# howland_vccs_differential.net
KiCad netlist of a schematic drawn in EAGLE
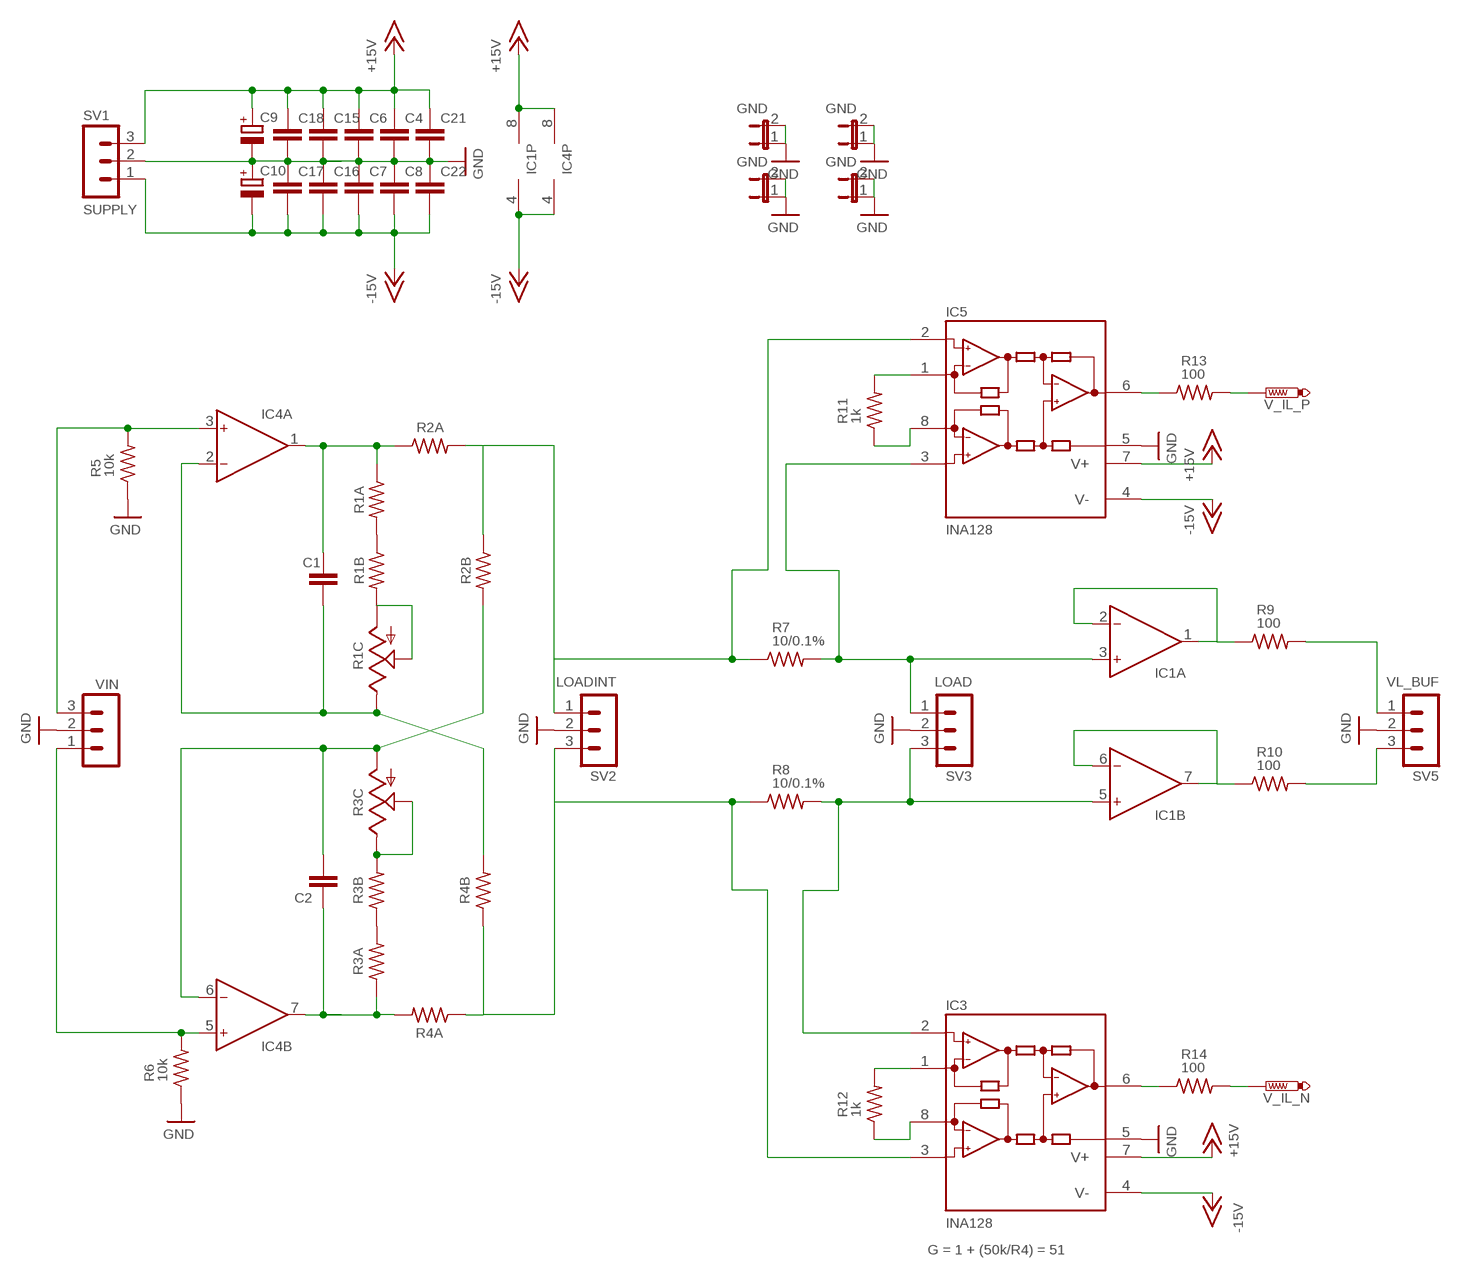
[diagram p0: schematic, sheet 1]

(export (version "E")
  (design (tool "Eeschema 10.0.6"))
  (components
    (comp (ref "C1")
      (value "C-EUC1206")
      (footprint "eagle-import:C1206")
      (libsource (lib "eagle-import") (part "C-EUC1206"))
    )
    (comp (ref "C2")
      (value "C-EUC1206")
      (footprint "eagle-import:C1206")
      (libsource (lib "eagle-import") (part "C-EUC1206"))
    )
    (comp (ref "C4")
      (value "C-EUC1206")
      (footprint "eagle-import:C1206")
      (libsource (lib "eagle-import") (part "C-EUC1206"))
    )
    (comp (ref "C6")
      (value "C-EUC1206")
      (footprint "eagle-import:C1206")
      (libsource (lib "eagle-import") (part "C-EUC1206"))
    )
    (comp (ref "C7")
      (value "C-EUC1206")
      (footprint "eagle-import:C1206")
      (libsource (lib "eagle-import") (part "C-EUC1206"))
    )
    (comp (ref "C8")
      (value "C-EUC1206")
      (footprint "eagle-import:C1206")
      (libsource (lib "eagle-import") (part "C-EUC1206"))
    )
    (comp (ref "C9")
      (value "CPOL-EUC/6032-28R")
      (footprint "eagle-import:C_6032-28R")
      (libsource (lib "eagle-import") (part "CPOL-EUC/6032-28R"))
    )
    (comp (ref "C10")
      (value "CPOL-EUC/6032-28R")
      (footprint "eagle-import:C_6032-28R")
      (libsource (lib "eagle-import") (part "CPOL-EUC/6032-28R"))
    )
    (comp (ref "C15")
      (value "C-EUC1206")
      (footprint "eagle-import:C1206")
      (libsource (lib "eagle-import") (part "C-EUC1206"))
    )
    (comp (ref "C16")
      (value "C-EUC1206")
      (footprint "eagle-import:C1206")
      (libsource (lib "eagle-import") (part "C-EUC1206"))
    )
    (comp (ref "C17")
      (value "C-EUC1206")
      (footprint "eagle-import:C1206")
      (libsource (lib "eagle-import") (part "C-EUC1206"))
    )
    (comp (ref "C18")
      (value "C-EUC1206")
      (footprint "eagle-import:C1206")
      (libsource (lib "eagle-import") (part "C-EUC1206"))
    )
    (comp (ref "C21")
      (value "C-EUC1206")
      (footprint "eagle-import:C1206")
      (libsource (lib "eagle-import") (part "C-EUC1206"))
    )
    (comp (ref "C22")
      (value "C-EUC1206")
      (footprint "eagle-import:C1206")
      (libsource (lib "eagle-import") (part "C-EUC1206"))
    )
    (comp (ref "IC1")
      (value "OPA2192")
      (footprint "eagle-import:SO8")
      (fields (field (name "MF") "ALTERA CORPORATION") (field (name "MPN") "AD826AR"))
      (libsource (lib "eagle-import") (part "AD826R"))
    )
    (comp (ref "IC3")
      (value "INA128")
      (footprint "eagle-import:SO08")
      (fields (field (name "MF") "TEXAS INSTRUMENTS") (field (name "MPN") "INA128U"))
      (libsource (lib "eagle-import") (part "INA128U"))
    )
    (comp (ref "IC4")
      (value "OPA2192")
      (footprint "eagle-import:SO8")
      (fields (field (name "MF") "ALTERA CORPORATION") (field (name "MPN") "AD826AR"))
      (libsource (lib "eagle-import") (part "AD826R"))
    )
    (comp (ref "IC5")
      (value "INA128")
      (footprint "eagle-import:SO08")
      (fields (field (name "MF") "TEXAS INSTRUMENTS") (field (name "MPN") "INA128U"))
      (libsource (lib "eagle-import") (part "INA128U"))
    )
    (comp (ref "JP8")
      (value "GND")
      (footprint "eagle-import:JP1")
      (libsource (lib "eagle-import") (part "JP1E"))
    )
    (comp (ref "JP10")
      (value "GND")
      (footprint "eagle-import:JP1")
      (libsource (lib "eagle-import") (part "JP1E"))
    )
    (comp (ref "JP11")
      (value "GND")
      (footprint "eagle-import:JP1")
      (libsource (lib "eagle-import") (part "JP1E"))
    )
    (comp (ref "JP12")
      (value "GND")
      (footprint "eagle-import:JP1")
      (libsource (lib "eagle-import") (part "JP1E"))
    )
    (comp (ref "R1A")
      (value "R-US_R1206")
      (footprint "eagle-import:R1206")
      (libsource (lib "eagle-import") (part "R-US_R1206"))
    )
    (comp (ref "R1B")
      (value "R-US_R1206")
      (footprint "eagle-import:R1206")
      (libsource (lib "eagle-import") (part "R-US_R1206"))
    )
    (comp (ref "R1C")
      (value "TRIM_US-3223J")
      (footprint "eagle-import:3223J")
      (libsource (lib "eagle-import") (part "TRIM_US-3223J"))
    )
    (comp (ref "R2A")
      (value "R-US_R1206")
      (footprint "eagle-import:R1206")
      (libsource (lib "eagle-import") (part "R-US_R1206"))
    )
    (comp (ref "R2B")
      (value "R-US_R1206")
      (footprint "eagle-import:R1206")
      (libsource (lib "eagle-import") (part "R-US_R1206"))
    )
    (comp (ref "R3A")
      (value "R-US_R1206")
      (footprint "eagle-import:R1206")
      (libsource (lib "eagle-import") (part "R-US_R1206"))
    )
    (comp (ref "R3B")
      (value "R-US_R1206")
      (footprint "eagle-import:R1206")
      (libsource (lib "eagle-import") (part "R-US_R1206"))
    )
    (comp (ref "R3C")
      (value "TRIM_US-3223J")
      (footprint "eagle-import:3223J")
      (libsource (lib "eagle-import") (part "TRIM_US-3223J"))
    )
    (comp (ref "R4A")
      (value "R-US_R1206")
      (footprint "eagle-import:R1206")
      (libsource (lib "eagle-import") (part "R-US_R1206"))
    )
    (comp (ref "R4B")
      (value "R-US_R1206")
      (footprint "eagle-import:R1206")
      (libsource (lib "eagle-import") (part "R-US_R1206"))
    )
    (comp (ref "R5")
      (value "10k")
      (footprint "eagle-import:R1206")
      (libsource (lib "eagle-import") (part "R-US_R1206"))
    )
    (comp (ref "R6")
      (value "10k")
      (footprint "eagle-import:R1206")
      (libsource (lib "eagle-import") (part "R-US_R1206"))
    )
    (comp (ref "R7")
      (value "10/0.1%")
      (footprint "eagle-import:R1206")
      (libsource (lib "eagle-import") (part "R-US_R1206"))
    )
    (comp (ref "R8")
      (value "10/0.1%")
      (footprint "eagle-import:R1206")
      (libsource (lib "eagle-import") (part "R-US_R1206"))
    )
    (comp (ref "R9")
      (value "100")
      (footprint "eagle-import:R1206")
      (libsource (lib "eagle-import") (part "R-US_R1206"))
    )
    (comp (ref "R10")
      (value "100")
      (footprint "eagle-import:R1206")
      (libsource (lib "eagle-import") (part "R-US_R1206"))
    )
    (comp (ref "R11")
      (value "1k")
      (footprint "eagle-import:R1206")
      (libsource (lib "eagle-import") (part "R-US_R1206"))
    )
    (comp (ref "R12")
      (value "1k")
      (footprint "eagle-import:R1206")
      (libsource (lib "eagle-import") (part "R-US_R1206"))
    )
    (comp (ref "R13")
      (value "100")
      (footprint "eagle-import:R1206")
      (libsource (lib "eagle-import") (part "R-US_R1206"))
    )
    (comp (ref "R14")
      (value "100")
      (footprint "eagle-import:R1206")
      (libsource (lib "eagle-import") (part "R-US_R1206"))
    )
    (comp (ref "SV1")
      (value "SUPPLY")
      (footprint "eagle-import:MA03-1")
      (libsource (lib "eagle-import") (part "MA03-1"))
    )
    (comp (ref "SV2")
      (value "LOADINT")
      (footprint "eagle-import:MA03-1")
      (libsource (lib "eagle-import") (part "sil_header_3_MA03-1"))
    )
    (comp (ref "SV3")
      (value "LOAD")
      (footprint "eagle-import:MA03-1")
      (libsource (lib "eagle-import") (part "sil_header_3_MA03-1"))
    )
    (comp (ref "SV5")
      (value "VL_BUF")
      (footprint "eagle-import:MA03-1")
      (libsource (lib "eagle-import") (part "sil_header_3_MA03-1"))
    )
    (comp (ref "VIN")
      (value "MA03-1")
      (footprint "eagle-import:MA03-1")
      (libsource (lib "eagle-import") (part "sil_header_3_MA03-1"))
    )
    (comp (ref "V_IL_N")
      (value "PTR1PAD1-13")
      (footprint "eagle-import:P1-13")
      (libsource (lib "eagle-import") (part "PTR1PAD1-13"))
    )
    (comp (ref "V_IL_P")
      (value "PTR1PAD1-13")
      (footprint "eagle-import:P1-13")
      (libsource (lib "eagle-import") (part "PTR1PAD1-13"))
    )
  )
  (nets
    (net (code "1") (name "+15V") (class "Default")
      (node (ref "C15") (pin "1") (pinfunction "1_1") (pintype "passive"))
      (node (ref "C18") (pin "1") (pinfunction "1_1") (pintype "passive"))
      (node (ref "C21") (pin "1") (pinfunction "1_1") (pintype "passive"))
      (node (ref "C4") (pin "1") (pinfunction "1_1") (pintype "passive"))
      (node (ref "C6") (pin "1") (pinfunction "1_1") (pintype "passive"))
      (node (ref "C9") (pin "+") (pinfunction "+_+") (pintype "passive"))
      (node (ref "IC1") (pin "8") (pinfunction "V+_8") (pintype "power_in"))
      (node (ref "IC3") (pin "7") (pinfunction "V+_7") (pintype "power_in"))
      (node (ref "IC4") (pin "8") (pinfunction "V+_8") (pintype "power_in"))
      (node (ref "IC5") (pin "7") (pinfunction "V+_7") (pintype "power_in"))
      (node (ref "SV1") (pin "3") (pinfunction "3_3") (pintype "passive"))
    )
    (net (code "2") (name "-15V") (class "Default")
      (node (ref "C10") (pin "-") (pinfunction "-_-") (pintype "passive"))
      (node (ref "C16") (pin "2") (pinfunction "2_2") (pintype "passive"))
      (node (ref "C17") (pin "2") (pinfunction "2_2") (pintype "passive"))
      (node (ref "C22") (pin "2") (pinfunction "2_2") (pintype "passive"))
      (node (ref "C7") (pin "2") (pinfunction "2_2") (pintype "passive"))
      (node (ref "C8") (pin "2") (pinfunction "2_2") (pintype "passive"))
      (node (ref "IC1") (pin "4") (pinfunction "V-_4") (pintype "power_in"))
      (node (ref "IC3") (pin "4") (pinfunction "V-_4") (pintype "power_in"))
      (node (ref "IC4") (pin "4") (pinfunction "V-_4") (pintype "power_in"))
      (node (ref "IC5") (pin "4") (pinfunction "V-_4") (pintype "power_in"))
      (node (ref "SV1") (pin "1") (pinfunction "1_1") (pintype "passive"))
    )
    (net (code "3") (name "GND") (class "Default")
      (node (ref "C10") (pin "+") (pinfunction "+_+") (pintype "passive"))
      (node (ref "C15") (pin "2") (pinfunction "2_2") (pintype "passive"))
      (node (ref "C16") (pin "1") (pinfunction "1_1") (pintype "passive"))
      (node (ref "C17") (pin "1") (pinfunction "1_1") (pintype "passive"))
      (node (ref "C18") (pin "2") (pinfunction "2_2") (pintype "passive"))
      (node (ref "C21") (pin "2") (pinfunction "2_2") (pintype "passive"))
      (node (ref "C22") (pin "1") (pinfunction "1_1") (pintype "passive"))
      (node (ref "C4") (pin "2") (pinfunction "2_2") (pintype "passive"))
      (node (ref "C6") (pin "2") (pinfunction "2_2") (pintype "passive"))
      (node (ref "C7") (pin "1") (pinfunction "1_1") (pintype "passive"))
      (node (ref "C8") (pin "1") (pinfunction "1_1") (pintype "passive"))
      (node (ref "C9") (pin "-") (pinfunction "-_-") (pintype "passive"))
      (node (ref "IC3") (pin "5") (pinfunction "REF_5") (pintype "passive"))
      (node (ref "IC5") (pin "5") (pinfunction "REF_5") (pintype "passive"))
      (node (ref "JP10") (pin "1") (pinfunction "1_1") (pintype "passive"))
      (node (ref "JP10") (pin "2") (pinfunction "2_2") (pintype "passive"))
      (node (ref "JP11") (pin "1") (pinfunction "1_1") (pintype "passive"))
      (node (ref "JP11") (pin "2") (pinfunction "2_2") (pintype "passive"))
      (node (ref "JP12") (pin "1") (pinfunction "1_1") (pintype "passive"))
      (node (ref "JP12") (pin "2") (pinfunction "2_2") (pintype "passive"))
      (node (ref "JP8") (pin "1") (pinfunction "1_1") (pintype "passive"))
      (node (ref "JP8") (pin "2") (pinfunction "2_2") (pintype "passive"))
      (node (ref "R5") (pin "1") (pinfunction "1_1") (pintype "passive"))
      (node (ref "R6") (pin "1") (pinfunction "1_1") (pintype "passive"))
      (node (ref "SV1") (pin "2") (pinfunction "2_2") (pintype "passive"))
      (node (ref "SV2") (pin "2") (pinfunction "2_2") (pintype "passive"))
      (node (ref "SV3") (pin "2") (pinfunction "2_2") (pintype "passive"))
      (node (ref "SV5") (pin "2") (pinfunction "2_2") (pintype "passive"))
      (node (ref "VIN") (pin "2") (pinfunction "2_2") (pintype "passive"))
    )
    (net (code "4") (name "Net-(IC1A-IN+)") (class "Default")
      (node (ref "IC1") (pin "3") (pinfunction "IN+_3") (pintype "input"))
      (node (ref "IC5") (pin "3") (pinfunction "+IN_3") (pintype "input"))
      (node (ref "R7") (pin "2") (pinfunction "2_2") (pintype "passive"))
      (node (ref "SV3") (pin "1") (pinfunction "1_1") (pintype "passive"))
    )
    (net (code "5") (name "Net-(IC1A-IN-)") (class "Default")
      (node (ref "IC1") (pin "1") (pinfunction "OUT_1") (pintype "output"))
      (node (ref "IC1") (pin "2") (pinfunction "IN-_2") (pintype "input"))
      (node (ref "R9") (pin "1") (pinfunction "1_1") (pintype "passive"))
    )
    (net (code "6") (name "Net-(IC1B-IN+)") (class "Default")
      (node (ref "IC1") (pin "5") (pinfunction "IN+_5") (pintype "input"))
      (node (ref "IC3") (pin "2") (pinfunction "-IN_2") (pintype "input"))
      (node (ref "R8") (pin "2") (pinfunction "2_2") (pintype "passive"))
      (node (ref "SV3") (pin "3") (pinfunction "3_3") (pintype "passive"))
    )
    (net (code "7") (name "Net-(IC1B-IN-)") (class "Default")
      (node (ref "IC1") (pin "6") (pinfunction "IN-_6") (pintype "input"))
      (node (ref "IC1") (pin "7") (pinfunction "OUT_7") (pintype "output"))
      (node (ref "R10") (pin "1") (pinfunction "1_1") (pintype "passive"))
    )
    (net (code "8") (name "Net-(IC3-+IN)") (class "Default")
      (node (ref "IC3") (pin "3") (pinfunction "+IN_3") (pintype "input"))
      (node (ref "R4A") (pin "1") (pinfunction "1_1") (pintype "passive"))
      (node (ref "R4B") (pin "1") (pinfunction "1_1") (pintype "passive"))
      (node (ref "R8") (pin "1") (pinfunction "1_1") (pintype "passive"))
      (node (ref "SV2") (pin "3") (pinfunction "3_3") (pintype "passive"))
    )
    (net (code "9") (name "Net-(IC3-OUT)") (class "Default")
      (node (ref "IC3") (pin "6") (pinfunction "OUT_6") (pintype "output"))
      (node (ref "R14") (pin "1") (pinfunction "1_1") (pintype "passive"))
    )
    (net (code "10") (name "Net-(IC3-RG-Pad1)") (class "Default")
      (node (ref "IC3") (pin "1") (pinfunction "RG_1") (pintype "passive"))
      (node (ref "R12") (pin "2") (pinfunction "2_2") (pintype "passive"))
    )
    (net (code "11") (name "Net-(IC3-RG-Pad8)") (class "Default")
      (node (ref "IC3") (pin "8") (pinfunction "RG_8") (pintype "passive"))
      (node (ref "R12") (pin "1") (pinfunction "1_1") (pintype "passive"))
    )
    (net (code "12") (name "Net-(IC4A-IN+)") (class "Default")
      (node (ref "IC4") (pin "3") (pinfunction "IN+_3") (pintype "input"))
      (node (ref "R5") (pin "2") (pinfunction "2_2") (pintype "passive"))
      (node (ref "VIN") (pin "3") (pinfunction "3_3") (pintype "passive"))
    )
    (net (code "13") (name "Net-(IC4A-IN-)") (class "Default")
      (node (ref "C1") (pin "2") (pinfunction "2_2") (pintype "passive"))
      (node (ref "IC4") (pin "2") (pinfunction "IN-_2") (pintype "input"))
      (node (ref "R1C") (pin "3") (pinfunction "E_3") (pintype "passive"))
      (node (ref "R4B") (pin "2") (pinfunction "2_2") (pintype "passive"))
    )
    (net (code "14") (name "Net-(IC4A-OUT)") (class "Default")
      (node (ref "C1") (pin "1") (pinfunction "1_1") (pintype "passive"))
      (node (ref "IC4") (pin "1") (pinfunction "OUT_1") (pintype "output"))
      (node (ref "R1A") (pin "1") (pinfunction "1_1") (pintype "passive"))
      (node (ref "R2A") (pin "1") (pinfunction "1_1") (pintype "passive"))
    )
    (net (code "15") (name "Net-(IC4B-IN+)") (class "Default")
      (node (ref "IC4") (pin "5") (pinfunction "IN+_5") (pintype "input"))
      (node (ref "R6") (pin "2") (pinfunction "2_2") (pintype "passive"))
      (node (ref "VIN") (pin "1") (pinfunction "1_1") (pintype "passive"))
    )
    (net (code "16") (name "Net-(IC4B-IN-)") (class "Default")
      (node (ref "C2") (pin "2") (pinfunction "2_2") (pintype "passive"))
      (node (ref "IC4") (pin "6") (pinfunction "IN-_6") (pintype "input"))
      (node (ref "R2B") (pin "2") (pinfunction "2_2") (pintype "passive"))
      (node (ref "R3C") (pin "1") (pinfunction "A_1") (pintype "passive"))
    )
    (net (code "17") (name "Net-(IC4B-OUT)") (class "Default")
      (node (ref "C2") (pin "1") (pinfunction "1_1") (pintype "passive"))
      (node (ref "IC4") (pin "7") (pinfunction "OUT_7") (pintype "output"))
      (node (ref "R3A") (pin "1") (pinfunction "1_1") (pintype "passive"))
      (node (ref "R4A") (pin "2") (pinfunction "2_2") (pintype "passive"))
    )
    (net (code "18") (name "Net-(IC5--IN)") (class "Default")
      (node (ref "IC5") (pin "2") (pinfunction "-IN_2") (pintype "input"))
      (node (ref "R2A") (pin "2") (pinfunction "2_2") (pintype "passive"))
      (node (ref "R2B") (pin "1") (pinfunction "1_1") (pintype "passive"))
      (node (ref "R7") (pin "1") (pinfunction "1_1") (pintype "passive"))
      (node (ref "SV2") (pin "1") (pinfunction "1_1") (pintype "passive"))
    )
    (net (code "19") (name "Net-(IC5-OUT)") (class "Default")
      (node (ref "IC5") (pin "6") (pinfunction "OUT_6") (pintype "output"))
      (node (ref "R13") (pin "1") (pinfunction "1_1") (pintype "passive"))
    )
    (net (code "20") (name "Net-(IC5-RG-Pad1)") (class "Default")
      (node (ref "IC5") (pin "1") (pinfunction "RG_1") (pintype "passive"))
      (node (ref "R11") (pin "2") (pinfunction "2_2") (pintype "passive"))
    )
    (net (code "21") (name "Net-(IC5-RG-Pad8)") (class "Default")
      (node (ref "IC5") (pin "8") (pinfunction "RG_8") (pintype "passive"))
      (node (ref "R11") (pin "1") (pinfunction "1_1") (pintype "passive"))
    )
    (net (code "22") (name "Net-(R1A-Pad2)") (class "Default")
      (node (ref "R1A") (pin "2") (pinfunction "2_2") (pintype "passive"))
      (node (ref "R1B") (pin "1") (pinfunction "1_1") (pintype "passive"))
    )
    (net (code "23") (name "Net-(R1C-A)") (class "Default")
      (node (ref "R1B") (pin "2") (pinfunction "2_2") (pintype "passive"))
      (node (ref "R1C") (pin "1") (pinfunction "A_1") (pintype "passive"))
      (node (ref "R1C") (pin "2") (pinfunction "S_2") (pintype "passive"))
    )
    (net (code "24") (name "Net-(R3A-Pad2)") (class "Default")
      (node (ref "R3A") (pin "2") (pinfunction "2_2") (pintype "passive"))
      (node (ref "R3B") (pin "1") (pinfunction "1_1") (pintype "passive"))
    )
    (net (code "25") (name "Net-(R3C-E)") (class "Default")
      (node (ref "R3B") (pin "2") (pinfunction "2_2") (pintype "passive"))
      (node (ref "R3C") (pin "2") (pinfunction "S_2") (pintype "passive"))
      (node (ref "R3C") (pin "3") (pinfunction "E_3") (pintype "passive"))
    )
    (net (code "26") (name "Net-(R9-Pad2)") (class "Default")
      (node (ref "R9") (pin "2") (pinfunction "2_2") (pintype "passive"))
      (node (ref "SV5") (pin "1") (pinfunction "1_1") (pintype "passive"))
    )
    (net (code "27") (name "Net-(R10-Pad2)") (class "Default")
      (node (ref "R10") (pin "2") (pinfunction "2_2") (pintype "passive"))
      (node (ref "SV5") (pin "3") (pinfunction "3_3") (pintype "passive"))
    )
    (net (code "28") (name "Net-(R13-Pad2)") (class "Default")
      (node (ref "R13") (pin "2") (pinfunction "2_2") (pintype "passive"))
      (node (ref "V_IL_P") (pin "TP") (pinfunction "TP_TP") (pintype "input"))
    )
    (net (code "29") (name "Net-(R14-Pad2)") (class "Default")
      (node (ref "R14") (pin "2") (pinfunction "2_2") (pintype "passive"))
      (node (ref "V_IL_N") (pin "TP") (pinfunction "TP_TP") (pintype "input"))
    )
  )
)
